# FMC_DAC_125M_14B_16CHA.net
KiCad netlist of a schematic drawn in Altium Designer
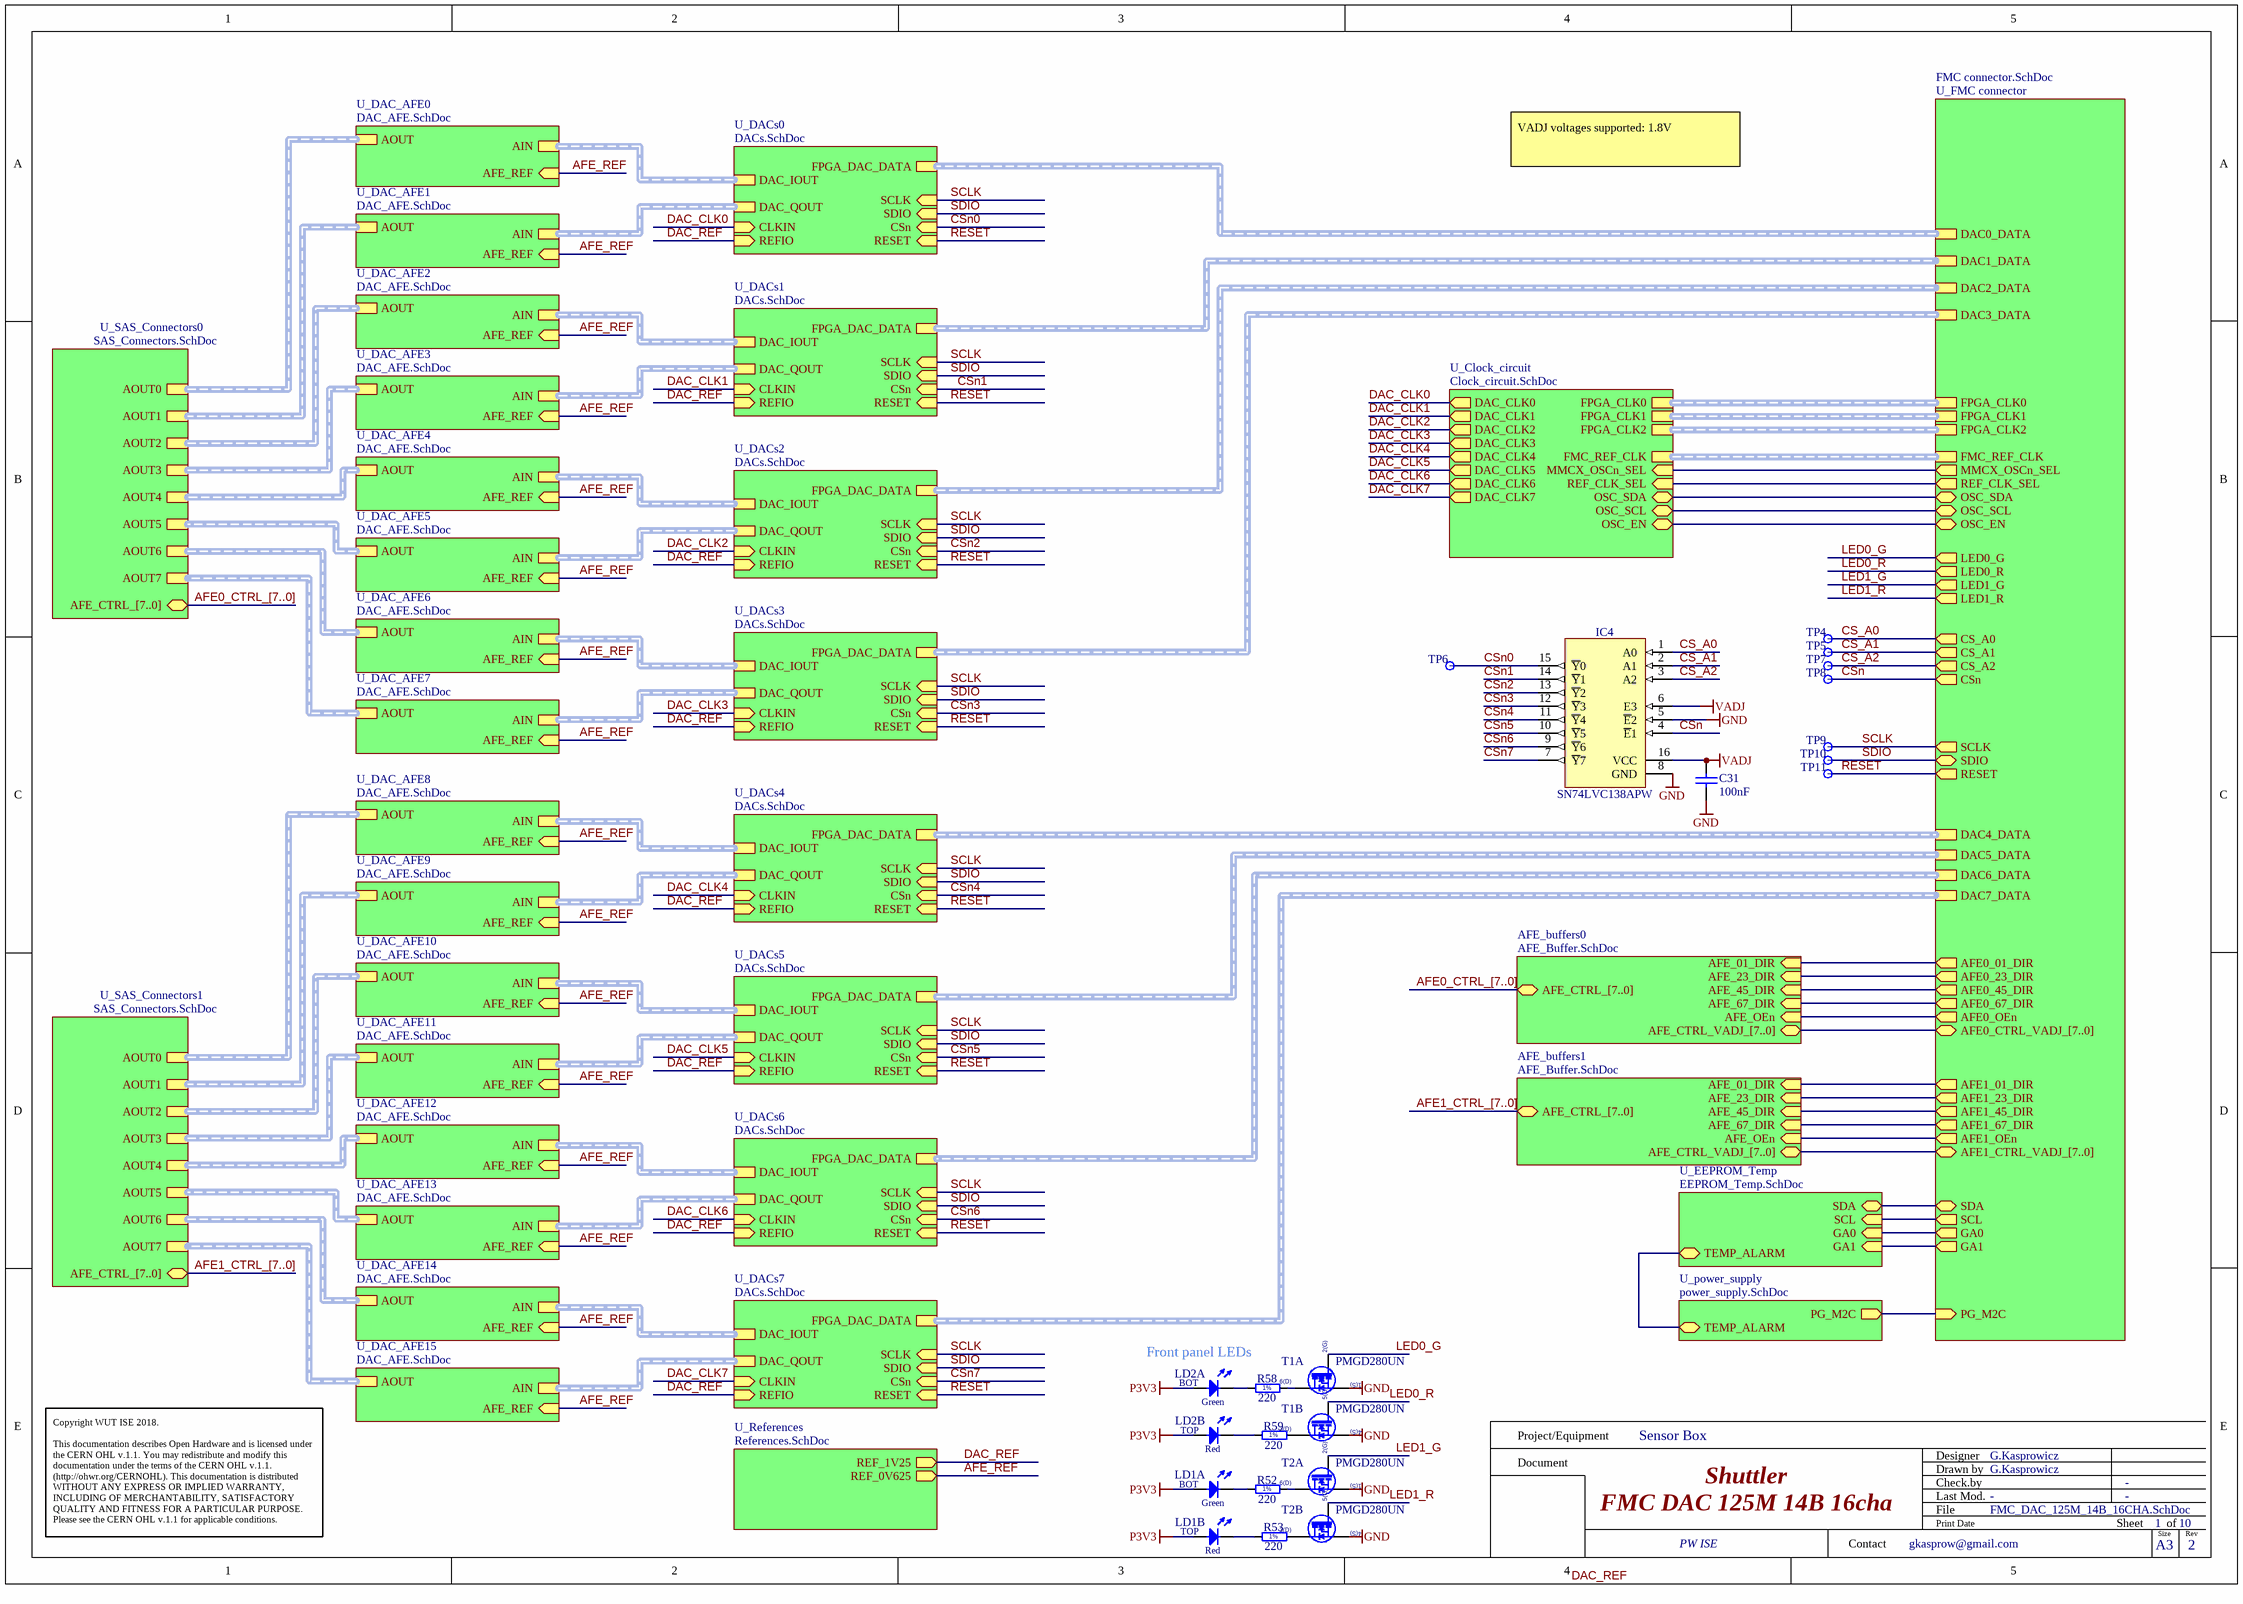
[diagram p0: FMC_DAC_125M_14B_16CHA.SchDoc]

(export (version "E")
  (design (tool "Eeschema 10.0.6"))
  (components
    (comp (ref "C31")
      (value "100nF")
      (footprint "CAPC1005X55N")
      (description "Non-polarised capacitor")
      (fields
        (field (name "PART NUMBER") "CC0402_100NF_16V_10%_X5R")
        (field (name "VOLTAGE") "16V")
        (field (name "AUTHOR") "CERN DEM JLC")
      )
      (libsource (lib "Capacitors") (part "Capacitor - non polarized"))
    )
    (comp (ref "IC4")
      (value "SN74LVC138APW")
      (footprint "SOP65P640X110-16N")
      (description "3-Line to 8-Line Decoder/Demultiplexer")
      (fields (field (name "MANUFACTURER") "Texas Instruments") (field (name "AUTHOR") "GK"))
      (libsource (lib "ICS-logic") (part "SN74LVC138APW"))
    )
    (comp (ref "LD1")
      (value "Red/Green")
      (footprint "LED_DIALIGHT_571-0112F")
      (description "2x LED  Botom Green, Top Red")
      (fields
        (field (name "PART NUMBER") "LED_DIALIGHT_571-0112F")
        (field (name "MANUFACTURER") "DIALIGHT")
        (field (name "AUTHOR") "CERN DEM JLC")
      )
      (libsource (lib "ICs And Semiconductors") (part "LED x2 G-1C2A-BOT_R-3C4A-TOP"))
    )
    (comp (ref "LD2")
      (value "Red/Green")
      (footprint "LED_DIALIGHT_571-0112F")
      (description "2x LED  Botom Green, Top Red")
      (fields
        (field (name "PART NUMBER") "LED_DIALIGHT_571-0112F")
        (field (name "MANUFACTURER") "DIALIGHT")
        (field (name "AUTHOR") "CERN DEM JLC")
      )
      (libsource (lib "ICs And Semiconductors") (part "LED x2 G-1C2A-BOT_R-3C4A-TOP"))
    )
    (comp (ref "R52")
      (value "220")
      (footprint "RESC1608X55N")
      (description "Resistor - 1%")
      (fields
        (field (name "PART NUMBER") "R0603_220R_1%_0.1W_100PPM")
        (field (name "POWER") "0.1W")
        (field (name "AUTHOR") "CERN DEM JLC")
      )
      (libsource (lib "Resistors") (part "Resistor - 1%"))
    )
    (comp (ref "R53")
      (value "220")
      (footprint "RESC1608X55N")
      (description "Resistor - 1%")
      (fields
        (field (name "PART NUMBER") "R0603_220R_1%_0.1W_100PPM")
        (field (name "POWER") "0.1W")
        (field (name "AUTHOR") "CERN DEM JLC")
      )
      (libsource (lib "Resistors") (part "Resistor - 1%"))
    )
    (comp (ref "R58")
      (value "220")
      (footprint "RESC1608X55N")
      (description "Resistor - 1%")
      (fields
        (field (name "PART NUMBER") "R0603_220R_1%_0.1W_100PPM")
        (field (name "POWER") "0.1W")
        (field (name "AUTHOR") "CERN DEM JLC")
      )
      (libsource (lib "Resistors") (part "Resistor - 1%"))
    )
    (comp (ref "R59")
      (value "220")
      (footprint "RESC1608X55N")
      (description "Resistor - 1%")
      (fields
        (field (name "PART NUMBER") "R0603_220R_1%_0.1W_100PPM")
        (field (name "POWER") "0.1W")
        (field (name "AUTHOR") "CERN DEM JLC")
      )
      (libsource (lib "Resistors") (part "Resistor - 1%"))
    )
    (comp (ref "T1")
      (value "PMGD280UN")
      (footprint "SOT65P210X110-6N")
      (description "Dual N-Channel micro TrenchMOS™ Ultra Low Level FET")
      (fields (field (name "MANUFACTURER") "NXP SEMICONDUCTORS") (field (name "AUTHOR") "CERN DEM JLC"))
      (libsource (lib "ICs And Semiconductors") (part "PMGD280UN"))
    )
    (comp (ref "T2")
      (value "PMGD280UN")
      (footprint "SOT65P210X110-6N")
      (description "Dual N-Channel micro TrenchMOS™ Ultra Low Level FET")
      (fields (field (name "MANUFACTURER") "NXP SEMICONDUCTORS") (field (name "AUTHOR") "CERN DEM JLC"))
      (libsource (lib "ICs And Semiconductors") (part "PMGD280UN"))
    )
    (comp (ref "TP4")
      (value "Test Point")
      (footprint "TPS127")
      (fields (field (name "PART NUMBER") "SMD_PAD_1.27X1.27MM") (field (name "AUTHOR") "CERN DEM JLC"))
      (libsource (lib "Eletro-mechanical") (part "Test Point"))
    )
    (comp (ref "TP5")
      (value "Test Point")
      (footprint "TPS127")
      (fields (field (name "PART NUMBER") "SMD_PAD_1.27X1.27MM") (field (name "AUTHOR") "CERN DEM JLC"))
      (libsource (lib "Eletro-mechanical") (part "Test Point"))
    )
    (comp (ref "TP6")
      (value "Test Point")
      (footprint "TPS127")
      (fields (field (name "PART NUMBER") "SMD_PAD_1.27X1.27MM") (field (name "AUTHOR") "CERN DEM JLC"))
      (libsource (lib "Eletro-mechanical") (part "Test Point"))
    )
    (comp (ref "TP7")
      (value "Test Point")
      (footprint "TPS127")
      (fields (field (name "PART NUMBER") "SMD_PAD_1.27X1.27MM") (field (name "AUTHOR") "CERN DEM JLC"))
      (libsource (lib "Eletro-mechanical") (part "Test Point"))
    )
    (comp (ref "TP8")
      (value "Test Point")
      (footprint "TPS127")
      (fields (field (name "PART NUMBER") "SMD_PAD_1.27X1.27MM") (field (name "AUTHOR") "CERN DEM JLC"))
      (libsource (lib "Eletro-mechanical") (part "Test Point"))
    )
    (comp (ref "TP9")
      (value "Test Point")
      (footprint "TPS127")
      (fields (field (name "PART NUMBER") "SMD_PAD_1.27X1.27MM") (field (name "AUTHOR") "CERN DEM JLC"))
      (libsource (lib "Eletro-mechanical") (part "Test Point"))
    )
    (comp (ref "TP10")
      (value "Test Point")
      (footprint "TPS127")
      (fields (field (name "PART NUMBER") "SMD_PAD_1.27X1.27MM") (field (name "AUTHOR") "CERN DEM JLC"))
      (libsource (lib "Eletro-mechanical") (part "Test Point"))
    )
    (comp (ref "TP11")
      (value "Test Point")
      (footprint "TPS127")
      (fields (field (name "PART NUMBER") "SMD_PAD_1.27X1.27MM") (field (name "AUTHOR") "CERN DEM JLC"))
      (libsource (lib "Eletro-mechanical") (part "Test Point"))
    )
  )
  (nets
    (net (code "64") (name "/CS_A0") (class "Default")
      (node (ref "IC4") (pin "1") (pinfunction "A0_1") (pintype "input"))
      (node (ref "TP4") (pin "1") (pinfunction "1_1") (pintype "bidirectional"))
    )
    (net (code "65") (name "/CS_A1") (class "Default")
      (node (ref "IC4") (pin "2") (pinfunction "A1_2") (pintype "input"))
      (node (ref "TP5") (pin "1") (pinfunction "1_1") (pintype "bidirectional"))
    )
    (net (code "66") (name "/CS_A2") (class "Default")
      (node (ref "IC4") (pin "3") (pinfunction "A2_3") (pintype "input"))
      (node (ref "TP7") (pin "1") (pinfunction "1_1") (pintype "bidirectional"))
    )
    (net (code "67") (name "/CSn") (class "Default")
      (node (ref "IC4") (pin "4") (pinfunction "~{E}1_4") (pintype "input"))
      (node (ref "TP8") (pin "1") (pinfunction "1_1") (pintype "bidirectional"))
    )
    (net (code "68") (name "/CSn0") (class "Default")
      (node (ref "IC4") (pin "15") (pinfunction "~{Y}0_15") (pintype "output"))
      (node (ref "TP6") (pin "1") (pinfunction "1_1") (pintype "bidirectional"))
    )
    (net (code "69") (name "/CSn1") (class "Default")
      (node (ref "IC4") (pin "14") (pinfunction "~{Y}1_14") (pintype "output"))
    )
    (net (code "70") (name "/CSn2") (class "Default")
      (node (ref "IC4") (pin "13") (pinfunction "~{Y}2_13") (pintype "output"))
    )
    (net (code "71") (name "/CSn3") (class "Default")
      (node (ref "IC4") (pin "12") (pinfunction "~{Y}3_12") (pintype "output"))
    )
    (net (code "72") (name "/CSn4") (class "Default")
      (node (ref "IC4") (pin "11") (pinfunction "~{Y}4_11") (pintype "output"))
    )
    (net (code "73") (name "/CSn5") (class "Default")
      (node (ref "IC4") (pin "10") (pinfunction "~{Y}5_10") (pintype "output"))
    )
    (net (code "74") (name "/CSn6") (class "Default")
      (node (ref "IC4") (pin "9") (pinfunction "~{Y}6_9") (pintype "output"))
    )
    (net (code "75") (name "/CSn7") (class "Default")
      (node (ref "IC4") (pin "7") (pinfunction "~{Y}7_7") (pintype "output"))
    )
    (net (code "99") (name "/LED0_G") (class "Default")
      (node (ref "T1") (pin "2") (pinfunction "G_2") (pintype "passive"))
    )
    (net (code "100") (name "/LED0_R") (class "Default")
      (node (ref "T1") (pin "5") (pinfunction "G_5") (pintype "passive"))
    )
    (net (code "101") (name "/LED1_G") (class "Default")
      (node (ref "T2") (pin "2") (pinfunction "G_2") (pintype "passive"))
    )
    (net (code "102") (name "/LED1_R") (class "Default")
      (node (ref "T2") (pin "5") (pinfunction "G_5") (pintype "passive"))
    )
    (net (code "109") (name "/RESET") (class "Default")
      (node (ref "TP11") (pin "1") (pinfunction "1_1") (pintype "bidirectional"))
    )
    (net (code "111") (name "/SCLK") (class "Default")
      (node (ref "TP9") (pin "1") (pinfunction "1_1") (pintype "bidirectional"))
    )
    (net (code "113") (name "/SDIO") (class "Default")
      (node (ref "TP10") (pin "1") (pinfunction "1_1") (pintype "bidirectional"))
    )
    (net (code "115") (name "GND") (class "Default")
      (node (ref "C31") (pin "1") (pinfunction "1_1") (pintype "passive"))
      (node (ref "IC4") (pin "5") (pinfunction "~{E}2_5") (pintype "input"))
      (node (ref "IC4") (pin "8") (pinfunction "GND_8") (pintype "power_in"))
      (node (ref "T1") (pin "1") (pinfunction "S_1") (pintype "passive"))
      (node (ref "T1") (pin "4") (pinfunction "S_4") (pintype "passive"))
      (node (ref "T2") (pin "1") (pinfunction "S_1") (pintype "passive"))
      (node (ref "T2") (pin "4") (pinfunction "S_4") (pintype "passive"))
    )
    (net (code "116") (name "Net-(LD1A-C)") (class "Default")
      (node (ref "LD1") (pin "1") (pinfunction "C_1") (pintype "passive"))
      (node (ref "R52") (pin "1") (pinfunction "1_1") (pintype "passive"))
    )
    (net (code "117") (name "Net-(LD1B-C)") (class "Default")
      (node (ref "LD1") (pin "3") (pinfunction "C_3") (pintype "passive"))
      (node (ref "R53") (pin "1") (pinfunction "1_1") (pintype "passive"))
    )
    (net (code "118") (name "Net-(LD2A-C)") (class "Default")
      (node (ref "LD2") (pin "1") (pinfunction "C_1") (pintype "passive"))
      (node (ref "R58") (pin "1") (pinfunction "1_1") (pintype "passive"))
    )
    (net (code "119") (name "Net-(LD2B-C)") (class "Default")
      (node (ref "LD2") (pin "3") (pinfunction "C_3") (pintype "passive"))
      (node (ref "R59") (pin "1") (pinfunction "1_1") (pintype "passive"))
    )
    (net (code "120") (name "Net-(T1A-D)") (class "Default")
      (node (ref "R58") (pin "2") (pinfunction "2_2") (pintype "passive"))
      (node (ref "T1") (pin "6") (pinfunction "D_6") (pintype "passive"))
    )
    (net (code "121") (name "Net-(T1B-D)") (class "Default")
      (node (ref "R59") (pin "2") (pinfunction "2_2") (pintype "passive"))
      (node (ref "T1") (pin "3") (pinfunction "D_3") (pintype "passive"))
    )
    (net (code "122") (name "Net-(T2A-D)") (class "Default")
      (node (ref "R52") (pin "2") (pinfunction "2_2") (pintype "passive"))
      (node (ref "T2") (pin "6") (pinfunction "D_6") (pintype "passive"))
    )
    (net (code "123") (name "Net-(T2B-D)") (class "Default")
      (node (ref "R53") (pin "2") (pinfunction "2_2") (pintype "passive"))
      (node (ref "T2") (pin "3") (pinfunction "D_3") (pintype "passive"))
    )
    (net (code "124") (name "P3V3") (class "Default")
      (node (ref "LD1") (pin "2") (pinfunction "A_2") (pintype "passive"))
      (node (ref "LD1") (pin "4") (pinfunction "A_4") (pintype "passive"))
      (node (ref "LD2") (pin "2") (pinfunction "A_2") (pintype "passive"))
      (node (ref "LD2") (pin "4") (pinfunction "A_4") (pintype "passive"))
    )
    (net (code "125") (name "VADJ") (class "Default")
      (node (ref "C31") (pin "2") (pinfunction "2_2") (pintype "passive"))
      (node (ref "IC4") (pin "16") (pinfunction "VCC_16") (pintype "power_in"))
      (node (ref "IC4") (pin "6") (pinfunction "E3_6") (pintype "input"))
    )
  )
)
